# ui_connector.net
KiCad netlist of a schematic drawn in EAGLE
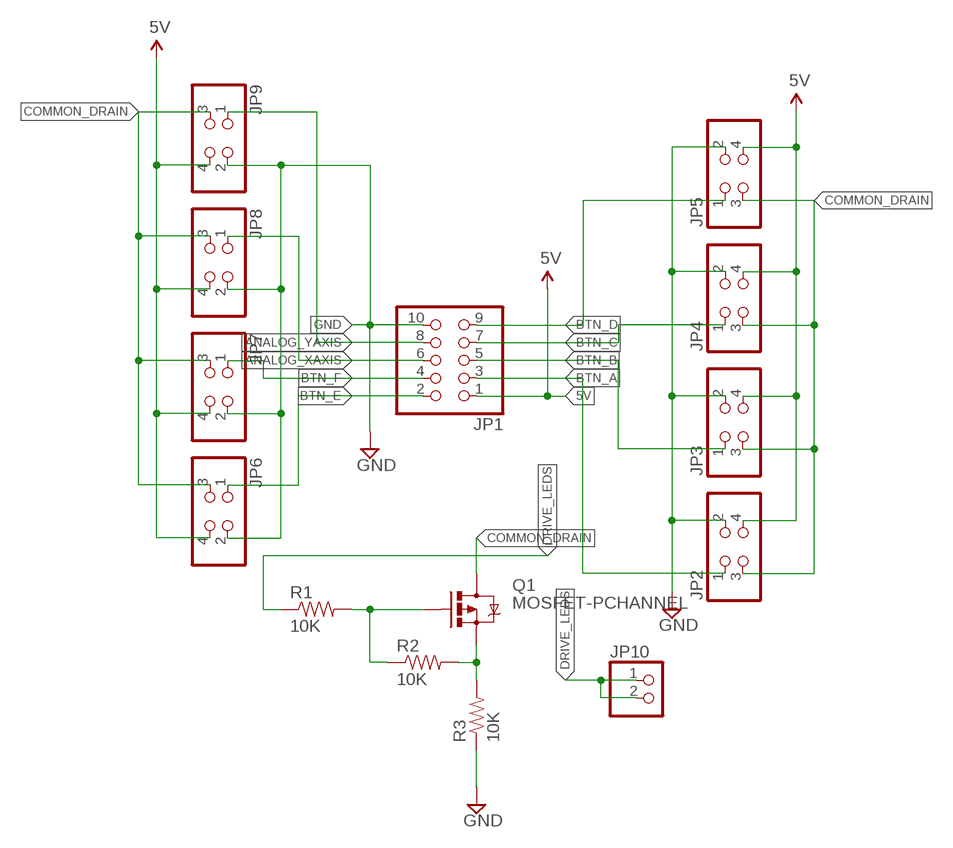
[diagram p0: schematic, sheet 1]

(export (version "E")
  (design (tool "Eeschema 10.0.6"))
  (components
    (comp (ref "JP1")
      (value "PINHD-2X5")
      (footprint "eagle-import:2X05")
      (libsource (lib "eagle-import") (part "PINHD-2X5"))
    )
    (comp (ref "JP2")
      (value "PINHD-2X2")
      (footprint "eagle-import:2X02")
      (libsource (lib "eagle-import") (part "PINHD-2X2"))
    )
    (comp (ref "JP3")
      (value "PINHD-2X2")
      (footprint "eagle-import:2X02")
      (libsource (lib "eagle-import") (part "PINHD-2X2"))
    )
    (comp (ref "JP4")
      (value "PINHD-2X2")
      (footprint "eagle-import:2X02")
      (libsource (lib "eagle-import") (part "PINHD-2X2"))
    )
    (comp (ref "JP5")
      (value "PINHD-2X2")
      (footprint "eagle-import:2X02")
      (libsource (lib "eagle-import") (part "PINHD-2X2"))
    )
    (comp (ref "JP6")
      (value "PINHD-2X2")
      (footprint "eagle-import:2X02")
      (libsource (lib "eagle-import") (part "PINHD-2X2"))
    )
    (comp (ref "JP7")
      (value "PINHD-2X2")
      (footprint "eagle-import:2X02")
      (libsource (lib "eagle-import") (part "PINHD-2X2"))
    )
    (comp (ref "JP8")
      (value "PINHD-2X2")
      (footprint "eagle-import:2X02")
      (libsource (lib "eagle-import") (part "PINHD-2X2"))
    )
    (comp (ref "JP9")
      (value "PINHD-2X2")
      (footprint "eagle-import:2X02")
      (libsource (lib "eagle-import") (part "PINHD-2X2"))
    )
    (comp (ref "JP10")
      (value "PINHD-1X2")
      (footprint "eagle-import:1X02")
      (libsource (lib "eagle-import") (part "PINHD-1X2"))
    )
    (comp (ref "Q1")
      (value "MOSFET-PCHANNEL")
      (footprint "eagle-import:SOT23-3")
      (libsource (lib "eagle-import") (part "MOSFET-PCHANNEL"))
    )
    (comp (ref "R1")
      (value "10K")
      (footprint "eagle-import:0805")
      (libsource (lib "eagle-import") (part "RESISTOR0805-RES"))
    )
    (comp (ref "R2")
      (value "10K")
      (footprint "eagle-import:0805")
      (libsource (lib "eagle-import") (part "RESISTOR0805-RES"))
    )
    (comp (ref "R3")
      (value "10K")
      (footprint "eagle-import:0805")
      (libsource (lib "eagle-import") (part "RESISTOR0805-RES"))
    )
  )
  (nets
    (net (code "1") (name "5V") (class "Default")
      (node (ref "JP1") (pin "1") (pinfunction "1_1") (pintype "passive"))
      (node (ref "JP2") (pin "4") (pinfunction "4_4") (pintype "passive"))
      (node (ref "JP3") (pin "4") (pinfunction "4_4") (pintype "passive"))
      (node (ref "JP4") (pin "4") (pinfunction "4_4") (pintype "passive"))
      (node (ref "JP5") (pin "4") (pinfunction "4_4") (pintype "passive"))
      (node (ref "JP6") (pin "4") (pinfunction "4_4") (pintype "passive"))
      (node (ref "JP7") (pin "4") (pinfunction "4_4") (pintype "passive"))
      (node (ref "JP8") (pin "4") (pinfunction "4_4") (pintype "passive"))
      (node (ref "JP9") (pin "4") (pinfunction "4_4") (pintype "passive"))
    )
    (net (code "2") (name "ANALOG_XAXIS") (class "Default")
      (node (ref "JP1") (pin "6") (pinfunction "6_6") (pintype "passive"))
      (node (ref "JP8") (pin "1") (pinfunction "1_1") (pintype "passive"))
    )
    (net (code "3") (name "ANALOG_YAXIS") (class "Default")
      (node (ref "JP1") (pin "8") (pinfunction "8_8") (pintype "passive"))
      (node (ref "JP9") (pin "1") (pinfunction "1_1") (pintype "passive"))
    )
    (net (code "4") (name "BTN_A") (class "Default")
      (node (ref "JP1") (pin "3") (pinfunction "3_3") (pintype "passive"))
      (node (ref "JP2") (pin "1") (pinfunction "1_1") (pintype "passive"))
    )
    (net (code "5") (name "BTN_B") (class "Default")
      (node (ref "JP1") (pin "5") (pinfunction "5_5") (pintype "passive"))
      (node (ref "JP3") (pin "1") (pinfunction "1_1") (pintype "passive"))
    )
    (net (code "6") (name "BTN_C") (class "Default")
      (node (ref "JP1") (pin "7") (pinfunction "7_7") (pintype "passive"))
      (node (ref "JP4") (pin "1") (pinfunction "1_1") (pintype "passive"))
    )
    (net (code "7") (name "BTN_D") (class "Default")
      (node (ref "JP1") (pin "9") (pinfunction "9_9") (pintype "passive"))
      (node (ref "JP5") (pin "1") (pinfunction "1_1") (pintype "passive"))
    )
    (net (code "8") (name "BTN_E") (class "Default")
      (node (ref "JP1") (pin "2") (pinfunction "2_2") (pintype "passive"))
      (node (ref "JP6") (pin "1") (pinfunction "1_1") (pintype "passive"))
    )
    (net (code "9") (name "BTN_F") (class "Default")
      (node (ref "JP1") (pin "4") (pinfunction "4_4") (pintype "passive"))
      (node (ref "JP7") (pin "1") (pinfunction "1_1") (pintype "passive"))
    )
    (net (code "10") (name "COMMON_DRAIN") (class "Default")
      (node (ref "JP2") (pin "3") (pinfunction "3_3") (pintype "passive"))
      (node (ref "JP3") (pin "3") (pinfunction "3_3") (pintype "passive"))
      (node (ref "JP4") (pin "3") (pinfunction "3_3") (pintype "passive"))
      (node (ref "JP5") (pin "3") (pinfunction "3_3") (pintype "passive"))
      (node (ref "JP6") (pin "3") (pinfunction "3_3") (pintype "passive"))
      (node (ref "JP7") (pin "3") (pinfunction "3_3") (pintype "passive"))
      (node (ref "JP8") (pin "3") (pinfunction "3_3") (pintype "passive"))
      (node (ref "JP9") (pin "3") (pinfunction "3_3") (pintype "passive"))
      (node (ref "Q1") (pin "3") (pinfunction "D_3") (pintype "passive"))
    )
    (net (code "11") (name "DRIVE_LEDS") (class "Default")
      (node (ref "JP10") (pin "1") (pinfunction "1_1") (pintype "passive"))
      (node (ref "JP10") (pin "2") (pinfunction "2_2") (pintype "passive"))
      (node (ref "R1") (pin "1") (pinfunction "1_1") (pintype "passive"))
    )
    (net (code "12") (name "GND") (class "Default")
      (node (ref "JP1") (pin "10") (pinfunction "10_10") (pintype "passive"))
      (node (ref "JP2") (pin "2") (pinfunction "2_2") (pintype "passive"))
      (node (ref "JP3") (pin "2") (pinfunction "2_2") (pintype "passive"))
      (node (ref "JP4") (pin "2") (pinfunction "2_2") (pintype "passive"))
      (node (ref "JP5") (pin "2") (pinfunction "2_2") (pintype "passive"))
      (node (ref "JP6") (pin "2") (pinfunction "2_2") (pintype "passive"))
      (node (ref "JP7") (pin "2") (pinfunction "2_2") (pintype "passive"))
      (node (ref "JP8") (pin "2") (pinfunction "2_2") (pintype "passive"))
      (node (ref "JP9") (pin "2") (pinfunction "2_2") (pintype "passive"))
      (node (ref "R3") (pin "1") (pinfunction "1_1") (pintype "passive"))
    )
    (net (code "13") (name "Net-(Q1-G)") (class "Default")
      (node (ref "Q1") (pin "1") (pinfunction "G_1") (pintype "passive"))
      (node (ref "R1") (pin "2") (pinfunction "2_2") (pintype "passive"))
      (node (ref "R2") (pin "1") (pinfunction "1_1") (pintype "passive"))
    )
    (net (code "14") (name "Net-(Q1-S)") (class "Default")
      (node (ref "Q1") (pin "2") (pinfunction "S_2") (pintype "passive"))
      (node (ref "R2") (pin "2") (pinfunction "2_2") (pintype "passive"))
      (node (ref "R3") (pin "2") (pinfunction "2_2") (pintype "passive"))
    )
  )
)
